# Juice_Rescue_v1_-_hw1_0_2.net
KiCad netlist of a schematic drawn in EAGLE
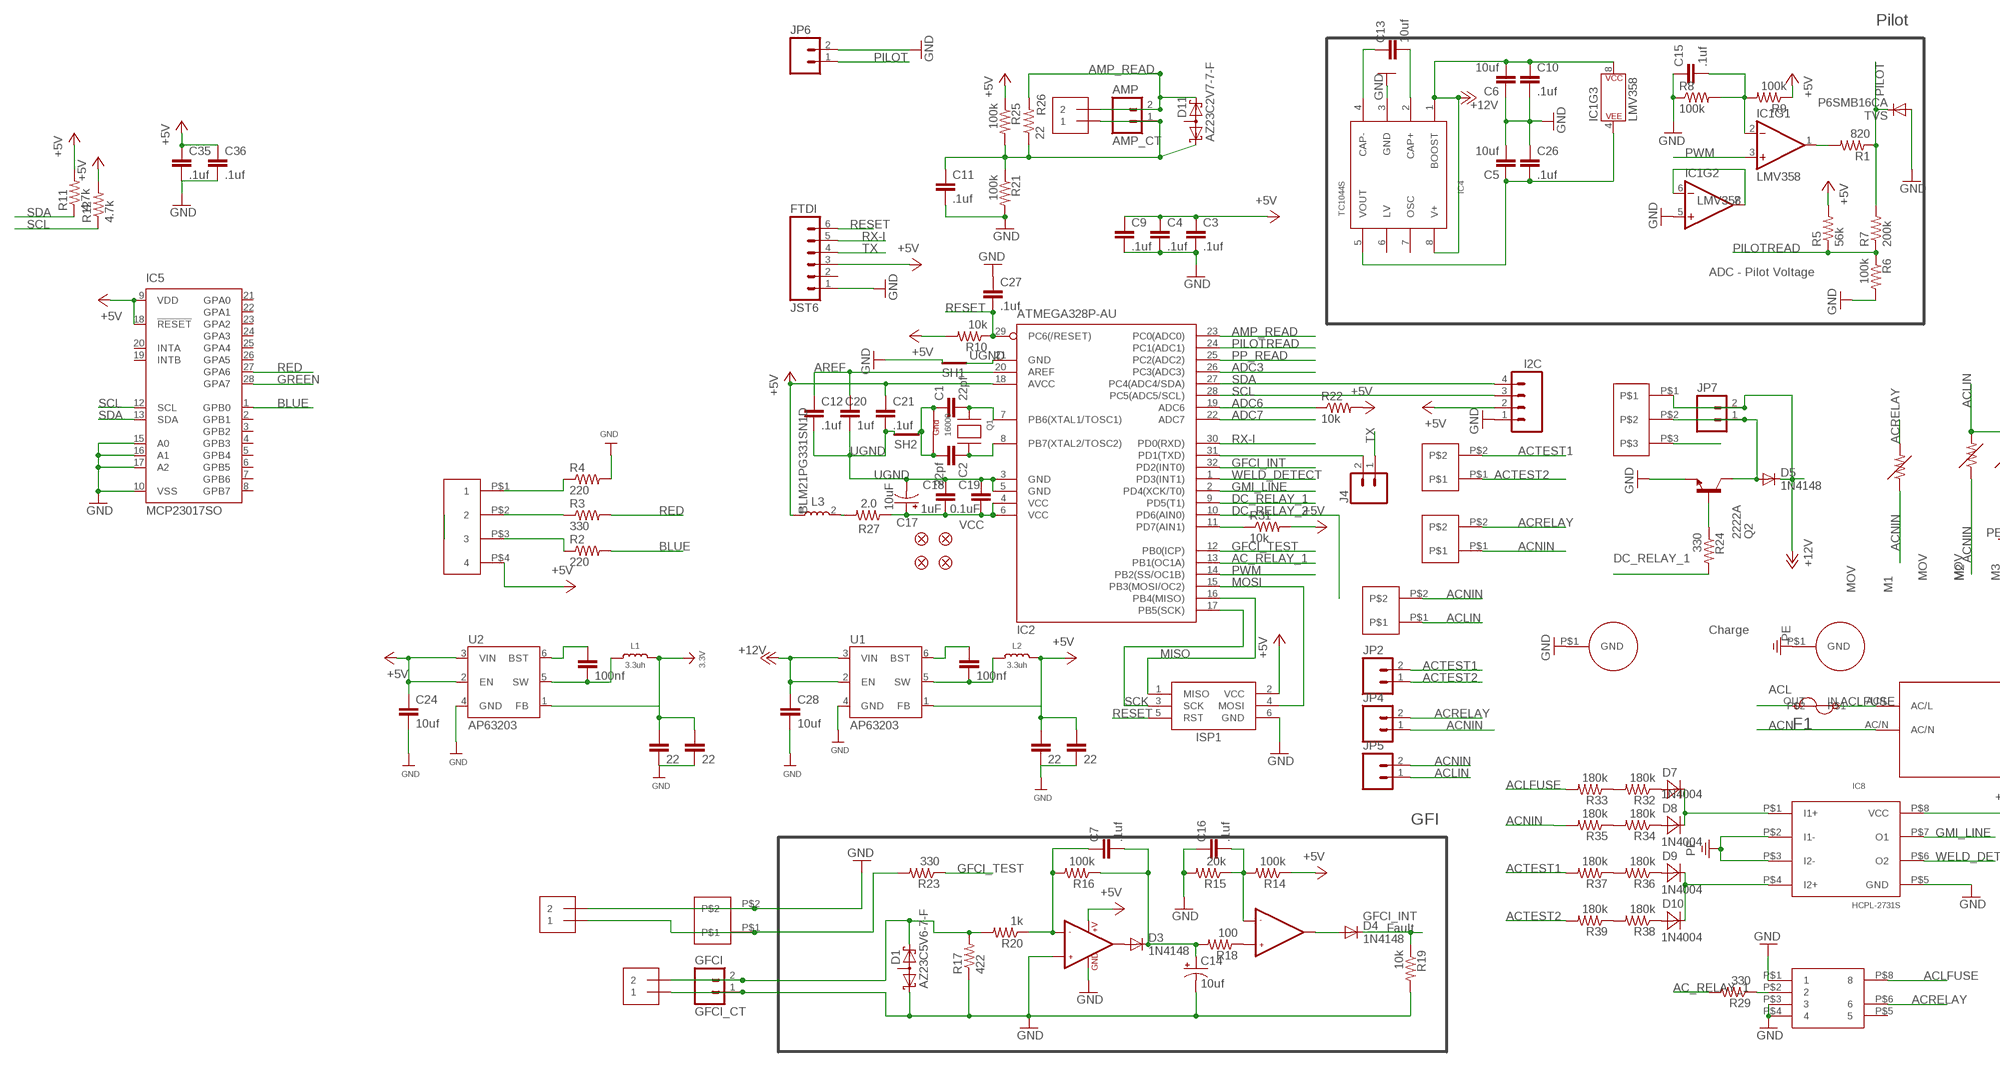
[diagram p0: schematic, sheet 1, part 1 of 2]
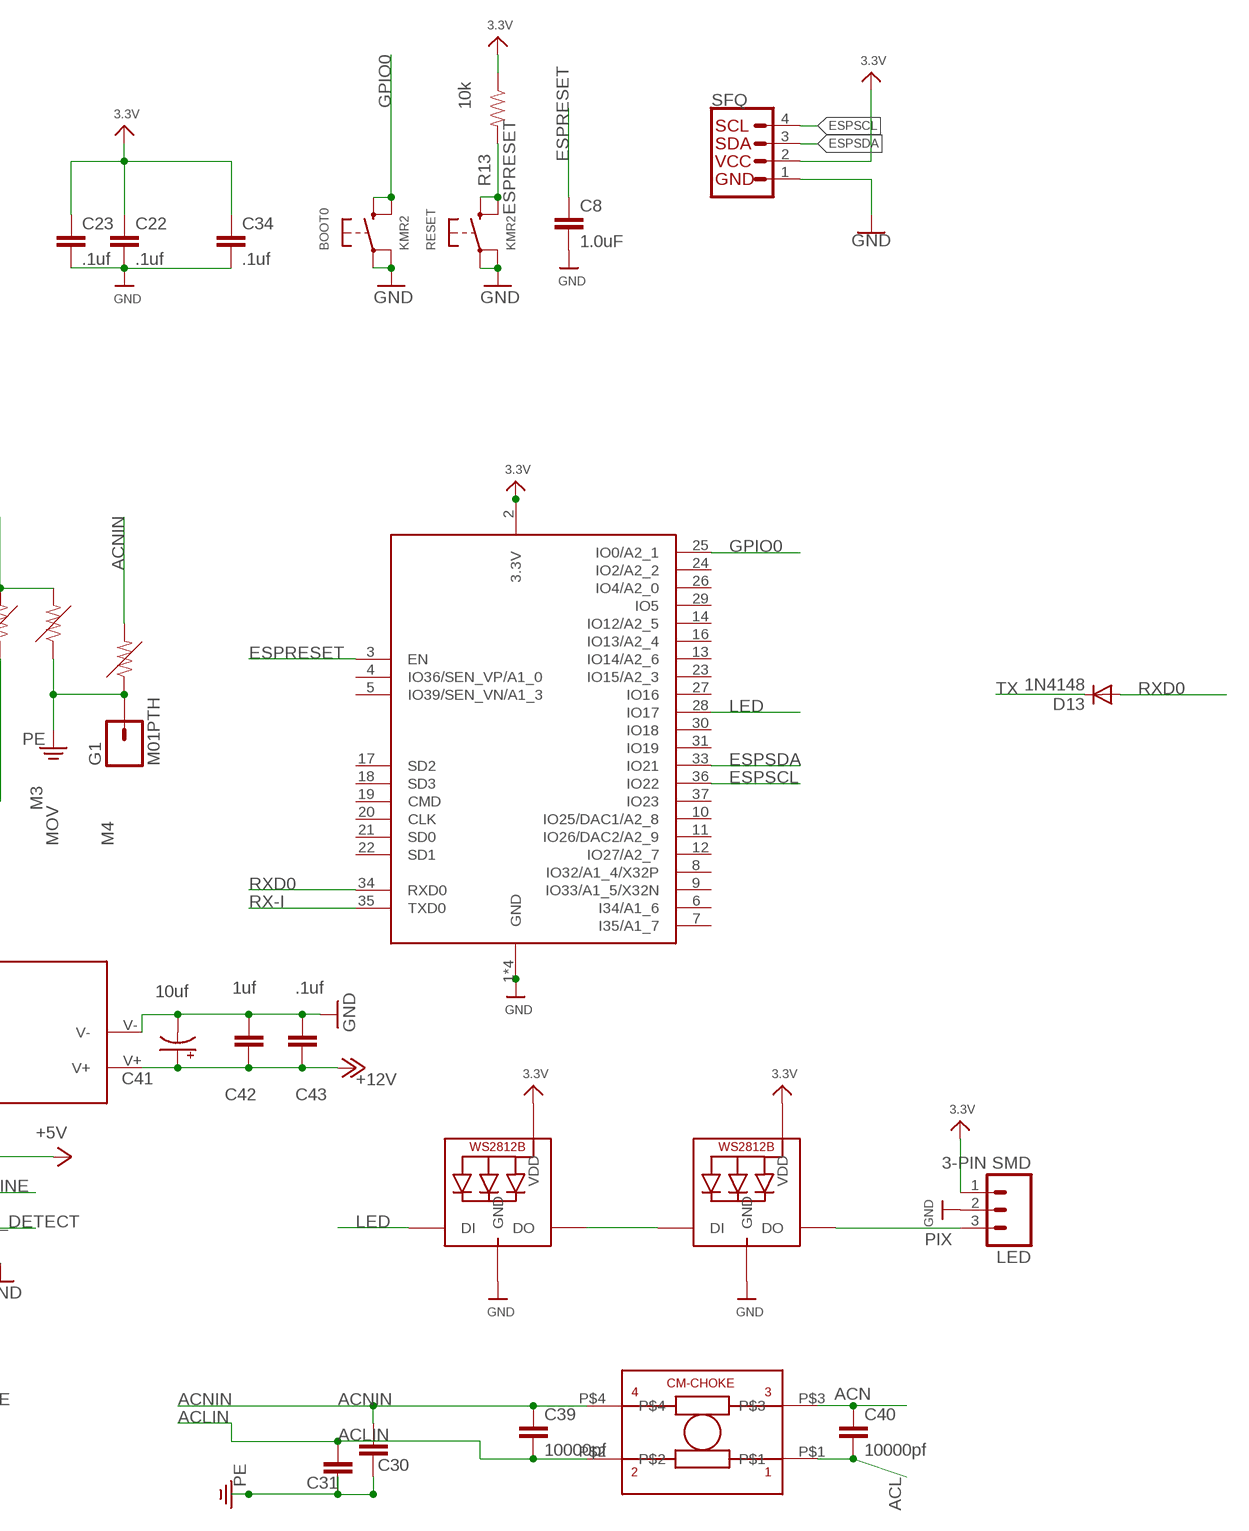
[diagram p1: schematic, sheet 1, part 2 of 2]

(export (version "E")
  (design (tool "Eeschema 10.0.6"))
  (components
    (comp (ref "AC")
      (value "AMPAC")
      (footprint "eagle-import:AMPAC")
      (libsource (lib "eagle-import") (part "AMPAC"))
    )
    (comp (ref "AC_RELAY")
      (value "AMPAC")
      (footprint "eagle-import:AMPAC")
      (libsource (lib "eagle-import") (part "AMPAC"))
    )
    (comp (ref "AC_TEST")
      (value "AMPAC")
      (footprint "eagle-import:AMPAC")
      (libsource (lib "eagle-import") (part "AMPAC"))
    )
    (comp (ref "AMP")
      (value "AMP_CT")
      (footprint "eagle-import:MOLEX_2")
      (libsource (lib "eagle-import") (part "MOLEX_2"))
    )
    (comp (ref "BOOT0")
      (value "KMR2")
      (footprint "eagle-import:BTN_KMR2_4.6X2.8")
      (libsource (lib "eagle-import") (part "SWITCH_TACT_SMT4.6X2.8"))
    )
    (comp (ref "C1")
      (value "22pf")
      (footprint "eagle-import:0805")
      (libsource (lib "eagle-import") (part "CAP0805"))
    )
    (comp (ref "C2")
      (value "22pf")
      (footprint "eagle-import:0805")
      (libsource (lib "eagle-import") (part "CAP0805"))
    )
    (comp (ref "C3")
      (value ".1uf")
      (footprint "eagle-import:0805")
      (libsource (lib "eagle-import") (part "CAP0805"))
    )
    (comp (ref "C4")
      (value ".1uf")
      (footprint "eagle-import:0805")
      (libsource (lib "eagle-import") (part "CAP0805"))
    )
    (comp (ref "C5")
      (value "10uf")
      (footprint "eagle-import:0805")
      (libsource (lib "eagle-import") (part "CAP0805"))
    )
    (comp (ref "C6")
      (value "10uf")
      (footprint "eagle-import:0805")
      (libsource (lib "eagle-import") (part "CAP0805"))
    )
    (comp (ref "C7")
      (value ".1uf")
      (footprint "eagle-import:0805")
      (libsource (lib "eagle-import") (part "CAP0805"))
    )
    (comp (ref "C8")
      (value "1.0uF")
      (footprint "eagle-import:0805")
      (libsource (lib "eagle-import") (part "1.0UF-0805-25V-(+80/-20%)"))
    )
    (comp (ref "C9")
      (value ".1uf")
      (footprint "eagle-import:0805")
      (libsource (lib "eagle-import") (part "CAP0805"))
    )
    (comp (ref "C10")
      (value ".1uf")
      (footprint "eagle-import:0805")
      (libsource (lib "eagle-import") (part "CAP0805"))
    )
    (comp (ref "C11")
      (value ".1uf")
      (footprint "eagle-import:0805")
      (libsource (lib "eagle-import") (part "CAP0805"))
    )
    (comp (ref "C12")
      (value ".1uf")
      (footprint "eagle-import:0805")
      (libsource (lib "eagle-import") (part "CAP0805"))
    )
    (comp (ref "C13")
      (value "10uf")
      (footprint "eagle-import:0805")
      (libsource (lib "eagle-import") (part "CAP0805"))
    )
    (comp (ref "C14")
      (value "10uf")
      (footprint "eagle-import:EIA3216")
      (libsource (lib "eagle-import") (part "CAP_POL1206"))
    )
    (comp (ref "C15")
      (value ".1uf")
      (footprint "eagle-import:0805")
      (libsource (lib "eagle-import") (part "CAP0805"))
    )
    (comp (ref "C16")
      (value ".1uf")
      (footprint "eagle-import:0805")
      (libsource (lib "eagle-import") (part "CAP0805"))
    )
    (comp (ref "C17")
      (value "10uF")
      (footprint "eagle-import:0603-POLAR")
      (libsource (lib "eagle-import") (part "10UF-POLAR-0603-6.3V-20%(TANT)"))
    )
    (comp (ref "C18")
      (value "1uF")
      (footprint "eagle-import:0805")
      (libsource (lib "eagle-import") (part "CAP0805"))
    )
    (comp (ref "C19")
      (value "0.1uF")
      (footprint "eagle-import:0805")
      (libsource (lib "eagle-import") (part "CAP0805"))
    )
    (comp (ref "C20")
      (value "1uf")
      (footprint "eagle-import:0805")
      (libsource (lib "eagle-import") (part "CAP0805"))
    )
    (comp (ref "C21")
      (value ".1uf")
      (footprint "eagle-import:0805")
      (libsource (lib "eagle-import") (part "CAP0805"))
    )
    (comp (ref "C22")
      (value ".1uf")
      (footprint "eagle-import:0805")
      (libsource (lib "eagle-import") (part "1.0UF-0805-25V-(+80/-20%)"))
    )
    (comp (ref "C23")
      (value ".1uf")
      (footprint "eagle-import:0805")
      (libsource (lib "eagle-import") (part "1.0UF-0805-25V-(+80/-20%)"))
    )
    (comp (ref "C24")
      (value "10uf")
      (footprint "eagle-import:0805")
      (libsource (lib "eagle-import") (part "1.0UF-0805-25V-(+80/-20%)"))
    )
    (comp (ref "C25")
      (value "22")
      (footprint "eagle-import:0805")
      (libsource (lib "eagle-import") (part "1.0UF-0805-25V-(+80/-20%)"))
    )
    (comp (ref "C26")
      (value ".1uf")
      (footprint "eagle-import:0805")
      (libsource (lib "eagle-import") (part "CAP0805"))
    )
    (comp (ref "C27")
      (value ".1uf")
      (footprint "eagle-import:0805")
      (libsource (lib "eagle-import") (part "CAP0805"))
    )
    (comp (ref "C28")
      (value "10uf")
      (footprint "eagle-import:0805")
      (libsource (lib "eagle-import") (part "1.0UF-0805-25V-(+80/-20%)"))
    )
    (comp (ref "C29")
      (value "22")
      (footprint "eagle-import:0805")
      (libsource (lib "eagle-import") (part "1.0UF-0805-25V-(+80/-20%)"))
    )
    (comp (ref "C30")
      (value "100nf")
      (footprint "eagle-import:0805")
      (libsource (lib "eagle-import") (part "1.0UF-0805-25V-(+80/-20%)"))
    )
    (comp (ref "C31")
      (value "22")
      (footprint "eagle-import:0805")
      (libsource (lib "eagle-import") (part "1.0UF-0805-25V-(+80/-20%)"))
    )
    (comp (ref "C32")
      (value "100nf")
      (footprint "eagle-import:0805")
      (libsource (lib "eagle-import") (part "1.0UF-0805-25V-(+80/-20%)"))
    )
    (comp (ref "C33")
      (value "22")
      (footprint "eagle-import:0805")
      (libsource (lib "eagle-import") (part "1.0UF-0805-25V-(+80/-20%)"))
    )
    (comp (ref "C34")
      (value ".1uf")
      (footprint "eagle-import:0805")
      (libsource (lib "eagle-import") (part "1.0UF-0805-25V-(+80/-20%)"))
    )
    (comp (ref "C35")
      (value ".1uf")
      (footprint "eagle-import:0805")
      (libsource (lib "eagle-import") (part "CAP0805"))
    )
    (comp (ref "C36")
      (value ".1uf")
      (footprint "eagle-import:0805")
      (libsource (lib "eagle-import") (part "CAP0805"))
    )
    (comp (ref "C37")
      (value "1000pf")
      (footprint "eagle-import:DK1E3EA")
      (libsource (lib "eagle-import") (part "DK1"))
    )
    (comp (ref "C38")
      (value "1000pf")
      (footprint "eagle-import:DK1E3EA")
      (libsource (lib "eagle-import") (part "DK1"))
    )
    (comp (ref "C39")
      (value "10000pf")
      (footprint "eagle-import:C7.5B4")
      (libsource (lib "eagle-import") (part "C7.5/4"))
    )
    (comp (ref "C40")
      (value "10000pf")
      (footprint "eagle-import:C7.5B4")
      (libsource (lib "eagle-import") (part "C7.5/4"))
    )
    (comp (ref "C41")
      (value "10uf")
      (footprint "eagle-import:EIA3216")
      (libsource (lib "eagle-import") (part "CAP_POL1206"))
    )
    (comp (ref "C42")
      (value "1uf")
      (footprint "eagle-import:0805")
      (libsource (lib "eagle-import") (part "CAP0805"))
    )
    (comp (ref "C43")
      (value ".1uf")
      (footprint "eagle-import:0805")
      (libsource (lib "eagle-import") (part "CAP0805"))
    )
    (comp (ref "D1")
      (value "AZ23C5V6-7-F")
      (footprint "eagle-import:SOT23")
      (libsource (lib "eagle-import") (part "BAS40-06"))
    )
    (comp (ref "D3")
      (value "1N4148")
      (footprint "eagle-import:SOD123")
      (libsource (lib "eagle-import") (part "DIODE-SOD123"))
    )
    (comp (ref "D4")
      (value "1N4148")
      (footprint "eagle-import:SOD123")
      (libsource (lib "eagle-import") (part "DIODE-SOD123"))
    )
    (comp (ref "D5")
      (value "1N4148")
      (footprint "eagle-import:SOD123")
      (libsource (lib "eagle-import") (part "DIODE-SOD123"))
    )
    (comp (ref "D7")
      (value "1N4004")
      (footprint "eagle-import:SMA")
      (libsource (lib "eagle-import") (part "MBRA340T3"))
    )
    (comp (ref "D8")
      (value "1N4004")
      (footprint "eagle-import:SMA")
      (libsource (lib "eagle-import") (part "MBRA340T3"))
    )
    (comp (ref "D9")
      (value "1N4004")
      (footprint "eagle-import:SMA")
      (libsource (lib "eagle-import") (part "MBRA340T3"))
    )
    (comp (ref "D10")
      (value "1N4004")
      (footprint "eagle-import:SMA")
      (libsource (lib "eagle-import") (part "MBRA340T3"))
    )
    (comp (ref "D11")
      (value "AZ23C2V7-7-F")
      (footprint "eagle-import:SOT23")
      (libsource (lib "eagle-import") (part "BAS40-06"))
    )
    (comp (ref "D13")
      (value "1N4148")
      (footprint "eagle-import:SOD123")
      (libsource (lib "eagle-import") (part "DIODE-SOD123"))
    )
    (comp (ref "F1")
      (value "BEL1.6AFUSE")
      (footprint "eagle-import:BELFUSE1A")
      (libsource (lib "eagle-import") (part "BEL1AFUSE"))
    )
    (comp (ref "FID1")
      (value "FIDUCIAL1X2.5")
      (footprint "eagle-import:FIDUCIAL-1X2.5")
      (libsource (lib "eagle-import") (part "FIDUCIAL1X2.5"))
    )
    (comp (ref "FID2")
      (value "FIDUCIAL1X2.5")
      (footprint "eagle-import:FIDUCIAL-1X2.5")
      (libsource (lib "eagle-import") (part "FIDUCIAL1X2.5"))
    )
    (comp (ref "FID3")
      (value "FIDUCIAL1X2.5")
      (footprint "eagle-import:FIDUCIAL-1X2.5")
      (libsource (lib "eagle-import") (part "FIDUCIAL1X2.5"))
    )
    (comp (ref "FID4")
      (value "FIDUCIAL1X2.5")
      (footprint "eagle-import:FIDUCIAL-1X2.5")
      (libsource (lib "eagle-import") (part "FIDUCIAL1X2.5"))
    )
    (comp (ref "FTDI")
      (value "JST6")
      (footprint "eagle-import:JST6")
      (libsource (lib "eagle-import") (part "JST6"))
    )
    (comp (ref "G1")
      (value "M01PTH")
      (footprint "eagle-import:1X01")
      (libsource (lib "eagle-import") (part "M01PTH"))
    )
    (comp (ref "GFCI")
      (value "GFCI_CT")
      (footprint "eagle-import:MOLEX_2")
      (libsource (lib "eagle-import") (part "MOLEX_2"))
    )
    (comp (ref "I2C")
      (value "M04JST-PTH-VERT")
      (footprint "eagle-import:JST-4-PTH-VERT")
      (libsource (lib "eagle-import") (part "M04JST-PTH-VERT"))
    )
    (comp (ref "IC1")
      (value "LMV358")
      (footprint "eagle-import:SO08")
      (libsource (lib "eagle-import") (part "LMV358SOIC"))
    )
    (comp (ref "IC2")
      (value "ATMEGA328P-AU")
      (footprint "eagle-import:TQFP32-08")
      (fields (field (name "MPN") "ATMEGA8-16AU"))
      (libsource (lib "eagle-import") (part "MEGA8-AI"))
    )
    (comp (ref "IC3")
      (value "LM358")
      (footprint "eagle-import:SO08")
      (libsource (lib "eagle-import") (part "LMV358"))
    )
    (comp (ref "IC4")
      (value "TC1044S")
      (footprint "eagle-import:SO-8")
      (libsource (lib "eagle-import") (part "TC1044S"))
    )
    (comp (ref "IC5")
      (value "MCP23017SO")
      (footprint "eagle-import:SO28W")
      (libsource (lib "eagle-import") (part "MCP23017SO"))
    )
    (comp (ref "IC7")
      (value "AQH2223")
      (footprint "eagle-import:SIL8")
      (libsource (lib "eagle-import") (part "AQH2223"))
    )
    (comp (ref "IC8")
      (value "HCPL-2731S")
      (footprint "eagle-import:SIL8-2")
      (libsource (lib "eagle-import") (part "HCPL-2731S"))
    )
    (comp (ref "ISP1")
      (value "ISP1")
      (footprint "eagle-import:AVRISP")
      (libsource (lib "eagle-import") (part "AVRISP-6"))
    )
    (comp (ref "J1")
      (value "1X2-3.5MM")
      (footprint "eagle-import:1X2-3.5MM")
      (libsource (lib "eagle-import") (part "1X2-3.5MM"))
    )
    (comp (ref "J2")
      (value "1X2-3.5MM")
      (footprint "eagle-import:1X2-3.5MM")
      (libsource (lib "eagle-import") (part "1X2-3.5MM"))
    )
    (comp (ref "J3")
      (value "1X2-3.5MM")
      (footprint "eagle-import:1X2-3.5MM")
      (libsource (lib "eagle-import") (part "1X2-3.5MM"))
    )
    (comp (ref "J4")
      (value "CONN_02")
      (footprint "eagle-import:1X02")
      (libsource (lib "eagle-import") (part "CONN_02"))
    )
    (comp (ref "JP2")
      (value "M025MM")
      (footprint "eagle-import:SCREWTERMINAL-5MM-2")
      (libsource (lib "eagle-import") (part "M025MM"))
    )
    (comp (ref "JP4")
      (value "M025MM")
      (footprint "eagle-import:SCREWTERMINAL-5MM-2")
      (libsource (lib "eagle-import") (part "M025MM"))
    )
    (comp (ref "JP5")
      (value "M025MM")
      (footprint "eagle-import:SCREWTERMINAL-5MM-2")
      (libsource (lib "eagle-import") (part "M025MM"))
    )
    (comp (ref "JP6")
      (value "M025MM")
      (footprint "eagle-import:SCREWTERMINAL-5MM-2")
      (libsource (lib "eagle-import") (part "M025MM"))
    )
    (comp (ref "JP7")
      (value "M025MM")
      (footprint "eagle-import:SCREWTERMINAL-5MM-2")
      (libsource (lib "eagle-import") (part "M025MM"))
    )
    (comp (ref "L1")
      (value "3.3uh")
      (footprint "eagle-import:MICROBUILDER_INDUCTOR_5X5MM_NR5040_NOTHERMALS")
      (libsource (lib "eagle-import") (part "MICROBUILDER_INDUCTORNR5040"))
    )
    (comp (ref "L2")
      (value "3.3uh")
      (footprint "eagle-import:MICROBUILDER_INDUCTOR_5X5MM_NR5040_NOTHERMALS")
      (libsource (lib "eagle-import") (part "MICROBUILDER_INDUCTORNR5040"))
    )
    (comp (ref "L3")
      (value "BLM21PG331SN1D")
      (footprint "eagle-import:INDC2012X87")
      (fields (field (name "MF") "Murata"))
      (libsource (lib "eagle-import") (part "BLM21PG331SN1D"))
    )
    (comp (ref "LED")
      (value "3-PIN SMD")
      (footprint "eagle-import:JST-3-SMD")
      (libsource (lib "eagle-import") (part "M03JST-SMD"))
    )
    (comp (ref "LED1")
      (value "WS2812B3535")
      (footprint "eagle-import:LED3535")
      (libsource (lib "eagle-import") (part "WS2812B3535"))
    )
    (comp (ref "LED2")
      (value "WS2812B3535")
      (footprint "eagle-import:LED3535")
      (libsource (lib "eagle-import") (part "WS2812B3535"))
    )
    (comp (ref "M1")
      (value "MOV")
      (footprint "eagle-import:MOV")
      (libsource (lib "eagle-import") (part "MOV"))
    )
    (comp (ref "M2")
      (value "MOV")
      (footprint "eagle-import:MOV")
      (libsource (lib "eagle-import") (part "MOV"))
    )
    (comp (ref "M3")
      (value "MOV")
      (footprint "eagle-import:MOV")
      (libsource (lib "eagle-import") (part "MOV"))
    )
    (comp (ref "M4")
      (value "MOV")
      (footprint "eagle-import:MOV")
      (libsource (lib "eagle-import") (part "MOV"))
    )
    (comp (ref "PILOT")
      (value "AMP3POS")
      (footprint "eagle-import:AMP3POS")
      (libsource (lib "eagle-import") (part "AMP3POS"))
    )
    (comp (ref "PS1")
      (value "IRM-10-5")
      (footprint "eagle-import:IRM-10-5")
      (libsource (lib "eagle-import") (part "IRM-10-5"))
    )
    (comp (ref "Q1")
      (value "16000")
      (footprint "eagle-import:NX3225")
      (libsource (lib "eagle-import") (part "XTAL-4-3225"))
    )
    (comp (ref "Q2")
      (value "2222A")
      (footprint "eagle-import:SOT23")
      (libsource (lib "eagle-import") (part "BCX70SMD"))
    )
    (comp (ref "R1")
      (value "820")
      (footprint "eagle-import:0805")
      (libsource (lib "eagle-import") (part "RESISTOR0805-RES"))
    )
    (comp (ref "R2")
      (value "220")
      (footprint "eagle-import:0805")
      (libsource (lib "eagle-import") (part "RESISTOR0805-RES"))
    )
    (comp (ref "R3")
      (value "330")
      (footprint "eagle-import:0805")
      (libsource (lib "eagle-import") (part "RESISTOR0805-RES"))
    )
    (comp (ref "R4")
      (value "220")
      (footprint "eagle-import:0805")
      (libsource (lib "eagle-import") (part "RESISTOR0805-RES"))
    )
    (comp (ref "R5")
      (value "56k")
      (footprint "eagle-import:0805")
      (libsource (lib "eagle-import") (part "RESISTOR0805-RES"))
    )
    (comp (ref "R6")
      (value "100k")
      (footprint "eagle-import:0805")
      (libsource (lib "eagle-import") (part "RESISTOR0805-RES"))
    )
    (comp (ref "R7")
      (value "200k")
      (footprint "eagle-import:0805")
      (libsource (lib "eagle-import") (part "RESISTOR0805-RES"))
    )
    (comp (ref "R8")
      (value "100k")
      (footprint "eagle-import:0805")
      (libsource (lib "eagle-import") (part "RESISTOR0805-RES"))
    )
    (comp (ref "R9")
      (value "100k")
      (footprint "eagle-import:0805")
      (libsource (lib "eagle-import") (part "RESISTOR0805-RES"))
    )
    (comp (ref "R10")
      (value "10k")
      (footprint "eagle-import:0805")
      (libsource (lib "eagle-import") (part "RESISTOR0805-RES"))
    )
    (comp (ref "R11")
      (value "4.7k")
      (footprint "eagle-import:0805")
      (libsource (lib "eagle-import") (part "RESISTOR0805-RES"))
    )
    (comp (ref "R12")
      (value "4.7k")
      (footprint "eagle-import:0805")
      (libsource (lib "eagle-import") (part "RESISTOR0805-RES"))
    )
    (comp (ref "R13")
      (value "10k")
      (footprint "eagle-import:0805")
      (libsource (lib "eagle-import") (part "RESISTOR0805"))
    )
    (comp (ref "R14")
      (value "100k")
      (footprint "eagle-import:0805")
      (libsource (lib "eagle-import") (part "RESISTOR0805-RES"))
    )
    (comp (ref "R15")
      (value "20k")
      (footprint "eagle-import:0805")
      (libsource (lib "eagle-import") (part "RESISTOR0805-RES"))
    )
    (comp (ref "R16")
      (value "100k")
      (footprint "eagle-import:0805")
      (libsource (lib "eagle-import") (part "RESISTOR0805-RES"))
    )
    (comp (ref "R17")
      (value "422")
      (footprint "eagle-import:0805")
      (libsource (lib "eagle-import") (part "RESISTOR0805-RES"))
    )
    (comp (ref "R18")
      (value "100")
      (footprint "eagle-import:0805")
      (libsource (lib "eagle-import") (part "RESISTOR0805-RES"))
    )
    (comp (ref "R19")
      (value "10k")
      (footprint "eagle-import:0805")
      (libsource (lib "eagle-import") (part "RESISTOR0805-RES"))
    )
    (comp (ref "R20")
      (value "1k")
      (footprint "eagle-import:0805")
      (libsource (lib "eagle-import") (part "RESISTOR0805-RES"))
    )
    (comp (ref "R21")
      (value "100k")
      (footprint "eagle-import:0805")
      (libsource (lib "eagle-import") (part "RESISTOR0805-RES"))
    )
    (comp (ref "R22")
      (value "10k")
      (footprint "eagle-import:0805")
      (libsource (lib "eagle-import") (part "RESISTOR0805-RES"))
    )
    (comp (ref "R23")
      (value "330")
      (footprint "eagle-import:0805")
      (libsource (lib "eagle-import") (part "RESISTOR0805-RES"))
    )
    (comp (ref "R24")
      (value "330")
      (footprint "eagle-import:0805")
      (libsource (lib "eagle-import") (part "RESISTOR0805-RES"))
    )
    (comp (ref "R25")
      (value "100k")
      (footprint "eagle-import:0805")
      (libsource (lib "eagle-import") (part "RESISTOR0805-RES"))
    )
    (comp (ref "R26")
      (value "22")
      (footprint "eagle-import:R1206")
      (libsource (lib "eagle-import") (part "R-US_R1206"))
    )
    (comp (ref "R27")
      (value "2.0")
      (footprint "eagle-import:0805")
      (libsource (lib "eagle-import") (part "RESISTOR0805-RES"))
    )
    (comp (ref "R29")
      (value "330")
      (footprint "eagle-import:0805")
      (libsource (lib "eagle-import") (part "RESISTOR0805-RES"))
    )
    (comp (ref "R31")
      (value "10k")
      (footprint "eagle-import:0805")
      (libsource (lib "eagle-import") (part "RESISTOR0805-RES"))
    )
    (comp (ref "R32")
      (value "180k")
      (footprint "eagle-import:1210")
      (libsource (lib "eagle-import") (part "0.1OHM-1/2W-1%(1210)"))
    )
    (comp (ref "R33")
      (value "180k")
      (footprint "eagle-import:1210")
      (libsource (lib "eagle-import") (part "0.1OHM-1/2W-1%(1210)"))
    )
    (comp (ref "R34")
      (value "180k")
      (footprint "eagle-import:1210")
      (libsource (lib "eagle-import") (part "0.1OHM-1/2W-1%(1210)"))
    )
    (comp (ref "R35")
      (value "180k")
      (footprint "eagle-import:1210")
      (libsource (lib "eagle-import") (part "0.1OHM-1/2W-1%(1210)"))
    )
    (comp (ref "R36")
      (value "180k")
      (footprint "eagle-import:1210")
      (libsource (lib "eagle-import") (part "0.1OHM-1/2W-1%(1210)"))
    )
    (comp (ref "R37")
      (value "180k")
      (footprint "eagle-import:1210")
      (libsource (lib "eagle-import") (part "0.1OHM-1/2W-1%(1210)"))
    )
    (comp (ref "R38")
      (value "180k")
      (footprint "eagle-import:1210")
      (libsource (lib "eagle-import") (part "0.1OHM-1/2W-1%(1210)"))
    )
    (comp (ref "R39")
      (value "180k")
      (footprint "eagle-import:1210")
      (libsource (lib "eagle-import") (part "0.1OHM-1/2W-1%(1210)"))
    )
    (comp (ref "RESET")
      (value "KMR2")
      (footprint "eagle-import:BTN_KMR2_4.6X2.8")
      (libsource (lib "eagle-import") (part "SWITCH_TACT_SMT4.6X2.8"))
    )
    (comp (ref "RF1")
      (value "RN214-0.3-02-47M")
      (footprint "eagle-import:RN214-0.3-02-47M")
      (libsource (lib "eagle-import") (part "RN214-0.3-02-47M"))
    )
    (comp (ref "RGB_LED")
      (value "4X1MMRIBBON")
      (footprint "eagle-import:4X1MMRIBBON")
      (libsource (lib "eagle-import") (part "4X1MMRIBBON"))
    )
    (comp (ref "SFQ")
      (value "QWIIC_CONNECTORJS-1MM")
      (footprint "eagle-import:JST04_1MM_RA")
      (libsource (lib "eagle-import") (part "QWIIC_CONNECTORJS-1MM"))
    )
    (comp (ref "SH1")
      (value "SHORT-HT5")
      (footprint "eagle-import:SHORT_TOP-50")
      (libsource (lib "eagle-import") (part "SHORT-HT5"))
    )
    (comp (ref "SH2")
      (value "SHORT-HT5")
      (footprint "eagle-import:SHORT_TOP-50")
      (libsource (lib "eagle-import") (part "SHORT-HT5"))
    )
    (comp (ref "TEST_COIL")
      (value "AMPAC")
      (footprint "eagle-import:AMPAC")
      (libsource (lib "eagle-import") (part "AMPAC"))
    )
    (comp (ref "TVS")
      (value "P6SMB16CA")
      (footprint "eagle-import:SMB")
      (libsource (lib "eagle-import") (part "DIODE-SMB"))
    )
    (comp (ref "U$3")
      (value "HOLE")
      (footprint "eagle-import:HOLE")
      (libsource (lib "eagle-import") (part "HOLE"))
    )
    (comp (ref "U$9")
      (value "HOLE")
      (footprint "eagle-import:HOLE")
      (libsource (lib "eagle-import") (part "HOLE"))
    )
    (comp (ref "U1")
      (value "AP63203")
      (footprint "eagle-import:SOT23-6")
      (libsource (lib "eagle-import") (part "AP63203"))
    )
    (comp (ref "U2")
      (value "AP63203")
      (footprint "eagle-import:SOT23-6")
      (libsource (lib "eagle-import") (part "AP63203"))
    )
    (comp (ref "X2")
      (value "ESP32-WROOM-32")
      (footprint "eagle-import:WROOM32_SKINNY")
      (libsource (lib "eagle-import") (part "ESP32_WROOM32_SKINNY"))
    )
  )
  (nets
    (net (code "1") (name "+5V") (class "Default")
      (node (ref "C21") (pin "1") (pinfunction "1_1") (pintype "passive"))
      (node (ref "C24") (pin "1") (pinfunction "1_1") (pintype "passive"))
      (node (ref "C29") (pin "1") (pinfunction "1_1") (pintype "passive"))
      (node (ref "C3") (pin "1") (pinfunction "1_1") (pintype "passive"))
      (node (ref "C33") (pin "1") (pinfunction "1_1") (pintype "passive"))
      (node (ref "C35") (pin "1") (pinfunction "1_1") (pintype "passive"))
      (node (ref "C36") (pin "1") (pinfunction "1_1") (pintype "passive"))
      (node (ref "C4") (pin "1") (pinfunction "1_1") (pintype "passive"))
      (node (ref "C9") (pin "1") (pinfunction "1_1") (pintype "passive"))
      (node (ref "FTDI") (pin "3") (pinfunction "3_3") (pintype "passive"))
      (node (ref "I2C") (pin "2") (pinfunction "2_2") (pintype "passive"))
      (node (ref "IC2") (pin "18") (pinfunction "AVCC_18") (pintype "power_in"))
      (node (ref "IC3") (pin "8") (pinfunction "+V_8") (pintype "power_in"))
      (node (ref "IC5") (pin "18") (pinfunction "~{RESET}_18") (pintype "input"))
      (node (ref "IC5") (pin "9") (pinfunction "VDD_9") (pintype "power_in"))
      (node (ref "IC8") (pin "P$8") (pinfunction "VCC_P$8") (pintype "bidirectional"))
      (node (ref "ISP1") (pin "2") (pinfunction "VCC_2") (pintype "power_in"))
      (node (ref "L2") (pin "P$2") (pinfunction "2_P$2") (pintype "passive"))
      (node (ref "L3") (pin "1") (pinfunction "1_1") (pintype "passive"))
      (node (ref "R10") (pin "2") (pinfunction "2_2") (pintype "passive"))
      (node (ref "R11") (pin "2") (pinfunction "2_2") (pintype "passive"))
      (node (ref "R12") (pin "2") (pinfunction "2_2") (pintype "passive"))
      (node (ref "R14") (pin "1") (pinfunction "1_1") (pintype "passive"))
      (node (ref "R22") (pin "2") (pinfunction "2_2") (pintype "passive"))
      (node (ref "R25") (pin "1") (pinfunction "1_1") (pintype "passive"))
      (node (ref "R31") (pin "2") (pinfunction "2_2") (pintype "passive"))
      (node (ref "R5") (pin "2") (pinfunction "2_2") (pintype "passive"))
      (node (ref "R9") (pin "1") (pinfunction "1_1") (pintype "passive"))
      (node (ref "RGB_LED") (pin "P$4") (pinfunction "4_P$4") (pintype "bidirectional"))
      (node (ref "U1") (pin "1") (pinfunction "FB_1") (pintype "bidirectional"))
      (node (ref "U2") (pin "2") (pinfunction "EN_2") (pintype "bidirectional"))
      (node (ref "U2") (pin "3") (pinfunction "VIN_3") (pintype "bidirectional"))
    )
    (net (code "2") (name "+12V") (class "Default")
      (node (ref "C10") (pin "1") (pinfunction "1_1") (pintype "passive"))
      (node (ref "C28") (pin "1") (pinfunction "1_1") (pintype "passive"))
      (node (ref "C41") (pin "A") (pinfunction "+_A") (pintype "passive"))
      (node (ref "C42") (pin "1") (pinfunction "1_1") (pintype "passive"))
      (node (ref "C43") (pin "2") (pinfunction "2_2") (pintype "passive"))
      (node (ref "C6") (pin "2") (pinfunction "2_2") (pintype "passive"))
      (node (ref "D5") (pin "C") (pinfunction "C_C") (pintype "passive"))
      (node (ref "IC1") (pin "8") (pinfunction "P$V+_8") (pintype "bidirectional"))
      (node (ref "IC4") (pin "1") (pinfunction "BOOST_1") (pintype "bidirectional"))
      (node (ref "IC4") (pin "8") (pinfunction "V+_8") (pintype "bidirectional"))
      (node (ref "JP7") (pin "2") (pinfunction "2_2") (pintype "passive"))
      (node (ref "PILOT") (pin "P$1") (pinfunction "P$1_P$1") (pintype "bidirectional"))
      (node (ref "PS1") (pin "V+") (pinfunction "V+_V+") (pintype "bidirectional"))
      (node (ref "U1") (pin "2") (pinfunction "EN_2") (pintype "bidirectional"))
      (node (ref "U1") (pin "3") (pinfunction "VIN_3") (pintype "bidirectional"))
    )
    (net (code "3") (name "/ACL") (class "Default")
      (node (ref "C40") (pin "2") (pinfunction "2_2") (pintype "passive"))
      (node (ref "F1") (pin "OUT") (pinfunction "P$1_OUT") (pintype "bidirectional"))
      (node (ref "RF1") (pin "P$1") (pinfunction "P$1_P$1") (pintype "bidirectional"))
    )
    (net (code "4") (name "/ACLFUSE") (class "Default")
      (node (ref "F1") (pin "IN") (pinfunction "P$2_IN") (pintype "bidirectional"))
      (node (ref "IC7") (pin "P$8") (pinfunction "8_P$8") (pintype "bidirectional"))
      (node (ref "PS1") (pin "AC/L") (pinfunction "AC/L_AC/L") (pintype "bidirectional"))
      (node (ref "R33") (pin "2") (pinfunction "2_2") (pintype "passive"))
    )
    (net (code "5") (name "/ACLIN") (class "Default")
      (node (ref "AC") (pin "P$1") (pinfunction "P$1_P$1") (pintype "bidirectional"))
      (node (ref "C38") (pin "P$2") (pinfunction "2_P$2") (pintype "passive"))
      (node (ref "C39") (pin "2") (pinfunction "2_2") (pintype "passive"))
      (node (ref "JP5") (pin "1") (pinfunction "1_1") (pintype "passive"))
      (node (ref "M2") (pin "P$2") (pinfunction "2_P$2") (pintype "passive"))
      (node (ref "M3") (pin "P$2") (pinfunction "2_P$2") (pintype "passive"))
      (node (ref "RF1") (pin "P$2") (pinfunction "P$2_P$2") (pintype "bidirectional"))
    )
    (net (code "6") (name "/ACN") (class "Default")
      (node (ref "C40") (pin "1") (pinfunction "1_1") (pintype "passive"))
      (node (ref "PS1") (pin "AC/N") (pinfunction "AC/N_AC/N") (pintype "bidirectional"))
      (node (ref "RF1") (pin "P$3") (pinfunction "P$3_P$3") (pintype "bidirectional"))
    )
    (net (code "7") (name "/ACNIN") (class "Default")
      (node (ref "AC") (pin "P$2") (pinfunction "P$2_P$2") (pintype "bidirectional"))
      (node (ref "AC_RELAY") (pin "P$1") (pinfunction "P$1_P$1") (pintype "bidirectional"))
      (node (ref "C37") (pin "P$2") (pinfunction "2_P$2") (pintype "passive"))
      (node (ref "C39") (pin "1") (pinfunction "1_1") (pintype "passive"))
      (node (ref "JP4") (pin "1") (pinfunction "1_1") (pintype "passive"))
      (node (ref "JP5") (pin "2") (pinfunction "2_2") (pintype "passive"))
      (node (ref "M1") (pin "P$1") (pinfunction "1_P$1") (pintype "passive"))
      (node (ref "M2") (pin "P$1") (pinfunction "1_P$1") (pintype "passive"))
      (node (ref "M4") (pin "P$2") (pinfunction "2_P$2") (pintype "passive"))
      (node (ref "R35") (pin "2") (pinfunction "2_2") (pintype "passive"))
      (node (ref "RF1") (pin "P$4") (pinfunction "P$4_P$4") (pintype "bidirectional"))
    )
    (net (code "8") (name "/ACRELAY") (class "Default")
      (node (ref "AC_RELAY") (pin "P$2") (pinfunction "P$2_P$2") (pintype "bidirectional"))
      (node (ref "IC7") (pin "P$6") (pinfunction "6_P$6") (pintype "bidirectional"))
      (node (ref "JP4") (pin "2") (pinfunction "2_2") (pintype "passive"))
      (node (ref "M1") (pin "P$2") (pinfunction "2_P$2") (pintype "passive"))
    )
    (net (code "9") (name "/ACTEST1") (class "Default")
      (node (ref "AC_TEST") (pin "P$2") (pinfunction "P$2_P$2") (pintype "bidirectional"))
      (node (ref "JP2") (pin "2") (pinfunction "2_2") (pintype "passive"))
      (node (ref "R37") (pin "2") (pinfunction "2_2") (pintype "passive"))
    )
    (net (code "10") (name "/ACTEST2") (class "Default")
      (node (ref "AC_TEST") (pin "P$1") (pinfunction "P$1_P$1") (pintype "bidirectional"))
      (node (ref "JP2") (pin "1") (pinfunction "1_1") (pintype "passive"))
      (node (ref "R39") (pin "2") (pinfunction "2_2") (pintype "passive"))
    )
    (net (code "11") (name "/AC_RELAY_1") (class "Default")
      (node (ref "IC2") (pin "13") (pinfunction "PB1(OC1A)_13") (pintype "bidirectional"))
      (node (ref "R29") (pin "2") (pinfunction "2_2") (pintype "passive"))
    )
    (net (code "12") (name "/ADC3") (class "Default")
      (node (ref "IC2") (pin "26") (pinfunction "PC3(ADC3)_26") (pintype "bidirectional"))
    )
    (net (code "13") (name "/ADC6") (class "Default")
      (node (ref "IC2") (pin "19") (pinfunction "ADC6_19") (pintype "bidirectional"))
      (node (ref "R22") (pin "1") (pinfunction "1_1") (pintype "passive"))
    )
    (net (code "14") (name "/ADC7") (class "Default")
      (node (ref "IC2") (pin "22") (pinfunction "ADC7_22") (pintype "bidirectional"))
    )
    (net (code "15") (name "/AMP_READ") (class "Default")
      (node (ref "AMP") (pin "2") (pinfunction "2_2") (pintype "passive"))
      (node (ref "D11") (pin "2") (pinfunction "K2_2") (pintype "passive"))
      (node (ref "IC2") (pin "23") (pinfunction "PC0(ADC0)_23") (pintype "bidirectional"))
      (node (ref "J3") (pin "2") (pinfunction "2_2") (pintype "passive"))
      (node (ref "R26") (pin "2") (pinfunction "2_2") (pintype "passive"))
    )
    (net (code "16") (name "/AREF") (class "Default")
      (node (ref "C12") (pin "1") (pinfunction "1_1") (pintype "passive"))
      (node (ref "C20") (pin "1") (pinfunction "1_1") (pintype "passive"))
      (node (ref "IC2") (pin "20") (pinfunction "AREF_20") (pintype "passive"))
    )
    (net (code "17") (name "/BLUE") (class "Default")
      (node (ref "IC5") (pin "1") (pinfunction "GPB0_1") (pintype "bidirectional"))
      (node (ref "R2") (pin "2") (pinfunction "2_2") (pintype "passive"))
    )
    (net (code "18") (name "/DC_RELAY_1") (class "Default")
      (node (ref "IC2") (pin "9") (pinfunction "PD5(T1)_9") (pintype "bidirectional"))
      (node (ref "R24") (pin "2") (pinfunction "2_2") (pintype "passive"))
    )
    (net (code "19") (name "/DC_RELAY_2") (class "Default")
      (node (ref "IC2") (pin "10") (pinfunction "PD6(AIN0)_10") (pintype "bidirectional"))
    )
    (net (code "20") (name "/ESPRESET") (class "Default")
      (node (ref "C8") (pin "1") (pinfunction "1_1") (pintype "passive"))
      (node (ref "R13") (pin "2") (pinfunction "2_2") (pintype "passive"))
      (node (ref "RESET") (pin "B") (pinfunction "S_B") (pintype "passive"))
      (node (ref "RESET") (pin "B'") (pinfunction "S1_B'") (pintype "passive"))
      (node (ref "X2") (pin "3") (pinfunction "EN_3") (pintype "input"))
    )
    (net (code "21") (name "/GFCI_INT") (class "Default")
      (node (ref "D4") (pin "C") (pinfunction "C_C") (pintype "passive"))
      (node (ref "IC2") (pin "32") (pinfunction "PD2(INT0)_32") (pintype "bidirectional"))
      (node (ref "R19") (pin "1") (pinfunction "1_1") (pintype "passive"))
    )
    (net (code "22") (name "/GFCI_TEST") (class "Default")
      (node (ref "IC2") (pin "12") (pinfunction "PB0(ICP)_12") (pintype "bidirectional"))
      (node (ref "R23") (pin "1") (pinfunction "1_1") (pintype "passive"))
    )
    (net (code "23") (name "/GMI_LINE") (class "Default")
      (node (ref "IC2") (pin "2") (pinfunction "PD4(XCK/T0)_2") (pintype "bidirectional"))
      (node (ref "IC8") (pin "P$7") (pinfunction "O1_P$7") (pintype "bidirectional"))
    )
    (net (code "24") (name "/GPIO0") (class "Default")
      (node (ref "BOOT0") (pin "B") (pinfunction "S_B") (pintype "passive"))
      (node (ref "BOOT0") (pin "B'") (pinfunction "S1_B'") (pintype "passive"))
      (node (ref "X2") (pin "25") (pinfunction "IO0/A2_1_25") (pintype "bidirectional"))
    )
    (net (code "25") (name "/GREEN") (class "Default")
      (node (ref "IC5") (pin "28") (pinfunction "GPA7_28") (pintype "bidirectional"))
    )
    (net (code "26") (name "/LED") (class "Default")
      (node (ref "LED1") (pin "1") (pinfunction "DI_1") (pintype "input"))
      (node (ref "X2") (pin "28") (pinfunction "IO17_28") (pintype "bidirectional"))
    )
    (net (code "27") (name "/MISO") (class "Default")
      (node (ref "IC2") (pin "16") (pinfunction "PB4(MISO)_16") (pintype "bidirectional"))
      (node (ref "ISP1") (pin "1") (pinfunction "MISO_1") (pintype "input"))
    )
    (net (code "28") (name "/MOSI") (class "Default")
      (node (ref "IC2") (pin "15") (pinfunction "PB3(MOSI/OC2)_15") (pintype "bidirectional"))
      (node (ref "ISP1") (pin "4") (pinfunction "MOSI_4") (pintype "output"))
    )
    (net (code "29") (name "/PILOT") (class "Default")
      (node (ref "JP6") (pin "1") (pinfunction "1_1") (pintype "passive"))
      (node (ref "PILOT") (pin "P$3") (pinfunction "P$3_P$3") (pintype "bidirectional"))
      (node (ref "R1") (pin "1") (pinfunction "1_1") (pintype "passive"))
      (node (ref "R7") (pin "2") (pinfunction "2_2") (pintype "passive"))
      (node (ref "TVS") (pin "C") (pinfunction "C_C") (pintype "passive"))
    )
    (net (code "30") (name "/PILOTREAD") (class "Default")
      (node (ref "IC2") (pin "24") (pinfunction "PC1(ADC1)_24") (pintype "bidirectional"))
      (node (ref "R5") (pin "1") (pinfunction "1_1") (pintype "passive"))
      (node (ref "R6") (pin "1") (pinfunction "1_1") (pintype "passive"))
      (node (ref "R7") (pin "1") (pinfunction "1_1") (pintype "passive"))
    )
    (net (code "31") (name "/PIX") (class "Default")
      (node (ref "LED") (pin "3") (pinfunction "3_3") (pintype "passive"))
      (node (ref "LED2") (pin "3") (pinfunction "DO_3") (pintype "output"))
    )
    (net (code "32") (name "/PP_READ") (class "Default")
      (node (ref "IC2") (pin "25") (pinfunction "PC2(ADC2)_25") (pintype "bidirectional"))
    )
    (net (code "33") (name "/PWM") (class "Default")
      (node (ref "IC1") (pin "3") (pinfunction "+IN_3") (pintype "input"))
      (node (ref "IC2") (pin "14") (pinfunction "PB2(SS/OC1B)_14") (pintype "bidirectional"))
    )
    (net (code "34") (name "/RED") (class "Default")
      (node (ref "IC5") (pin "27") (pinfunction "GPA6_27") (pintype "bidirectional"))
      (node (ref "R3") (pin "2") (pinfunction "2_2") (pintype "passive"))
    )
    (net (code "35") (name "/RESET") (class "Default")
      (node (ref "C27") (pin "2") (pinfunction "2_2") (pintype "passive"))
      (node (ref "FTDI") (pin "6") (pinfunction "6_6") (pintype "passive"))
      (node (ref "IC2") (pin "29") (pinfunction "PC6(/RESET)_29") (pintype "bidirectional"))
      (node (ref "ISP1") (pin "5") (pinfunction "RST_5") (pintype "output"))
      (node (ref "R10") (pin "1") (pinfunction "1_1") (pintype "passive"))
    )
    (net (code "36") (name "/RX-I") (class "Default")
      (node (ref "FTDI") (pin "5") (pinfunction "5_5") (pintype "passive"))
      (node (ref "IC2") (pin "30") (pinfunction "PD0(RXD)_30") (pintype "bidirectional"))
      (node (ref "X2") (pin "35") (pinfunction "TXD0_35") (pintype "output"))
    )
    (net (code "37") (name "/RXD0") (class "Default")
      (node (ref "D13") (pin "A") (pinfunction "A_A") (pintype "passive"))
      (node (ref "X2") (pin "34") (pinfunction "RXD0_34") (pintype "input"))
    )
    (net (code "38") (name "/SCK") (class "Default")
      (node (ref "IC2") (pin "17") (pinfunction "PB5(SCK)_17") (pintype "bidirectional"))
      (node (ref "ISP1") (pin "3") (pinfunction "SCK_3") (pintype "output"))
    )
    (net (code "39") (name "/SCL") (class "Default")
      (node (ref "I2C") (pin "3") (pinfunction "3_3") (pintype "passive"))
      (node (ref "IC2") (pin "28") (pinfunction "PC5(ADC5/SCL)_28") (pintype "bidirectional"))
      (node (ref "IC5") (pin "12") (pinfunction "SCL_12") (pintype "input"))
      (node (ref "R12") (pin "1") (pinfunction "1_1") (pintype "passive"))
    )
    (net (code "40") (name "/SDA") (class "Default")
      (node (ref "I2C") (pin "4") (pinfunction "4_4") (pintype "passive"))
      (node (ref "IC2") (pin "27") (pinfunction "PC4(ADC4/SDA)_27") (pintype "bidirectional"))
      (node (ref "IC5") (pin "13") (pinfunction "SDA_13") (pintype "bidirectional"))
      (node (ref "R11") (pin "1") (pinfunction "1_1") (pintype "passive"))
    )
    (net (code "41") (name "/TX") (class "Default")
      (node (ref "D13") (pin "C") (pinfunction "C_C") (pintype "passive"))
      (node (ref "FTDI") (pin "4") (pinfunction "4_4") (pintype "passive"))
      (node (ref "J4") (pin "1") (pinfunction "1_1") (pintype "passive"))
    )
    (net (code "42") (name "/UGND") (class "Default")
      (node (ref "C12") (pin "2") (pinfunction "2_2") (pintype "passive"))
      (node (ref "C17") (pin "-") (pinfunction "-_-") (pintype "passive"))
      (node (ref "C18") (pin "1") (pinfunction "1_1") (pintype "passive"))
      (node (ref "C19") (pin "1") (pinfunction "1_1") (pintype "passive"))
      (node (ref "C20") (pin "2") (pinfunction "2_2") (pintype "passive"))
      (node (ref "C21") (pin "2") (pinfunction "2_2") (pintype "passive"))
      (node (ref "IC2") (pin "21") (pinfunction "GND_21") (pintype "power_in"))
      (node (ref "IC2") (pin "3") (pinfunction "GND_3") (pintype "power_in"))
      (node (ref "IC2") (pin "5") (pinfunction "GND_5") (pintype "power_in"))
      (node (ref "SH1") (pin "1") (pinfunction "P$1_1") (pintype "bidirectional"))
      (node (ref "SH2") (pin "2") (pinfunction "P$2_2") (pintype "bidirectional"))
    )
    (net (code "43") (name "/VCC") (class "Default")
      (node (ref "C17") (pin "+") (pinfunction "+_+") (pintype "passive"))
      (node (ref "C18") (pin "2") (pinfunction "2_2") (pintype "passive"))
      (node (ref "C19") (pin "2") (pinfunction "2_2") (pintype "passive"))
      (node (ref "IC2") (pin "4") (pinfunction "VCC_4") (pintype "power_in"))
      (node (ref "IC2") (pin "6") (pinfunction "VCC_6") (pintype "power_in"))
      (node (ref "R27") (pin "1") (pinfunction "1_1") (pintype "passive"))
    )
    (net (code "44") (name "/WELD_DETECT") (class "Default")
      (node (ref "IC2") (pin "1") (pinfunction "PD3(INT1)_1") (pintype "bidirectional"))
      (node (ref "IC8") (pin "P$6") (pinfunction "O2_P$6") (pintype "bidirectional"))
    )
    (net (code "45") (name "3.3V") (class "Default")
      (node (ref "C22") (pin "1") (pinfunction "1_1") (pintype "passive"))
      (node (ref "C23") (pin "1") (pinfunction "1_1") (pintype "passive"))
      (node (ref "C25") (pin "1") (pinfunction "1_1") (pintype "passive"))
      (node (ref "C31") (pin "1") (pinfunction "1_1") (pintype "passive"))
      (node (ref "C34") (pin "1") (pinfunction "1_1") (pintype "passive"))
      (node (ref "L1") (pin "P$2") (pinfunction "2_P$2") (pintype "passive"))
      (node (ref "LED") (pin "1") (pinfunction "1_1") (pintype "passive"))
      (node (ref "LED1") (pin "2") (pinfunction "VDD_2") (pintype "power_in"))
      (node (ref "LED2") (pin "2") (pinfunction "VDD_2") (pintype "power_in"))
      (node (ref "R13") (pin "1") (pinfunction "1_1") (pintype "passive"))
      (node (ref "SFQ") (pin "2") (pinfunction "2_2") (pintype "power_in"))
      (node (ref "U2") (pin "1") (pinfunction "FB_1") (pintype "bidirectional"))
      (node (ref "X2") (pin "2") (pinfunction "3.3V_2") (pintype "passive"))
    )
    (net (code "46") (name "ESPSCL") (class "Default")
      (node (ref "SFQ") (pin "4") (pinfunction "4_4") (pintype "passive"))
      (node (ref "X2") (pin "36") (pinfunction "IO22_36") (pintype "bidirectional"))
    )
    (net (code "47") (name "ESPSDA") (class "Default")
      (node (ref "SFQ") (pin "3") (pinfunction "3_3") (pintype "passive"))
      (node (ref "X2") (pin "33") (pinfunction "IO21_33") (pintype "bidirectional"))
    )
    (net (code "48") (name "GND") (class "Default")
      (node (ref "BOOT0") (pin "A") (pinfunction "P_A") (pintype "passive"))
      (node (ref "BOOT0") (pin "A'") (pinfunction "P1_A'") (pintype "passive"))
      (node (ref "C10") (pin "2") (pinfunction "2_2") (pintype "passive"))
      (node (ref "C11") (pin "2") (pinfunction "2_2") (pintype "passive"))
      (node (ref "C14") (pin "C") (pinfunction "-_C") (pintype "passive"))
      (node (ref "C15") (pin "1") (pinfunction "1_1") (pintype "passive"))
      (node (ref "C16") (pin "1") (pinfunction "1_1") (pintype "passive"))
      (node (ref "C22") (pin "2") (pinfunction "2_2") (pintype "passive"))
      (node (ref "C23") (pin "2") (pinfunction "2_2") (pintype "passive"))
      (node (ref "C24") (pin "2") (pinfunction "2_2") (pintype "passive"))
      (node (ref "C25") (pin "2") (pinfunction "2_2") (pintype "passive"))
      (node (ref "C26") (pin "1") (pinfunction "1_1") (pintype "passive"))
      (node (ref "C27") (pin "1") (pinfunction "1_1") (pintype "passive"))
      (node (ref "C28") (pin "2") (pinfunction "2_2") (pintype "passive"))
      (node (ref "C29") (pin "2") (pinfunction "2_2") (pintype "passive"))
      (node (ref "C3") (pin "2") (pinfunction "2_2") (pintype "passive"))
      (node (ref "C31") (pin "2") (pinfunction "2_2") (pintype "passive"))
      (node (ref "C33") (pin "2") (pinfunction "2_2") (pintype "passive"))
      (node (ref "C34") (pin "2") (pinfunction "2_2") (pintype "passive"))
      (node (ref "C35") (pin "2") (pinfunction "2_2") (pintype "passive"))
      (node (ref "C36") (pin "2") (pinfunction "2_2") (pintype "passive"))
      (node (ref "C4") (pin "2") (pinfunction "2_2") (pintype "passive"))
      (node (ref "C41") (pin "C") (pinfunction "-_C") (pintype "passive"))
      (node (ref "C42") (pin "2") (pinfunction "2_2") (pintype "passive"))
      (node (ref "C43") (pin "1") (pinfunction "1_1") (pintype "passive"))
      (node (ref "C5") (pin "2") (pinfunction "2_2") (pintype "passive"))
      (node (ref "C6") (pin "1") (pinfunction "1_1") (pintype "passive"))
      (node (ref "C8") (pin "2") (pinfunction "2_2") (pintype "passive"))
      (node (ref "C9") (pin "2") (pinfunction "2_2") (pintype "passive"))
      (node (ref "D1") (pin "1") (pinfunction "K1_1") (pintype "passive"))
      (node (ref "FTDI") (pin "1") (pinfunction "1_1") (pintype "passive"))
      (node (ref "GFCI") (pin "1") (pinfunction "1_1") (pintype "passive"))
      (node (ref "I2C") (pin "1") (pinfunction "1_1") (pintype "passive"))
      (node (ref "IC1") (pin "5") (pinfunction "+IN_5") (pintype "input"))
      (node (ref "IC3") (pin "3") (pinfunction "+IN1_3") (pintype "input"))
      (node (ref "IC3") (pin "4") (pinfunction "GND_4") (pintype "power_in"))
      (node (ref "IC4") (pin "3") (pinfunction "GND_3") (pintype "bidirectional"))
      (node (ref "IC5") (pin "10") (pinfunction "VSS_10") (pintype "power_in"))
      (node (ref "IC5") (pin "15") (pinfunction "A0_15") (pintype "input"))
      (node (ref "IC5") (pin "16") (pinfunction "A1_16") (pintype "input"))
      (node (ref "IC5") (pin "17") (pinfunction "A2_17") (pintype "input"))
      (node (ref "IC7") (pin "P$1") (pinfunction "1_P$1") (pintype "bidirectional"))
      (node (ref "IC7") (pin "P$3") (pinfunction "3_P$3") (pintype "bidirectional"))
      (node (ref "IC7") (pin "P$4") (pinfunction "4_P$4") (pintype "bidirectional"))
      (node (ref "IC8") (pin "P$5") (pinfunction "GND_P$5") (pintype "bidirectional"))
      (node (ref "ISP1") (pin "6") (pinfunction "GND_6") (pintype "power_in"))
      (node (ref "J1") (pin "1") (pinfunction "1_1") (pintype "passive"))
      (node (ref "J2") (pin "2") (pinfunction "2_2") (pintype "passive"))
      (node (ref "JP6") (pin "2") (pinfunction "2_2") (pintype "passive"))
      (node (ref "LED") (pin "2") (pinfunction "2_2") (pintype "passive"))
      (node (ref "LED1") (pin "4") (pinfunction "GND_4") (pintype "power_in"))
      (node (ref "LED2") (pin "4") (pinfunction "GND_4") (pintype "power_in"))
      (node (ref "PS1") (pin "V-") (pinfunction "V-_V-") (pintype "bidirectional"))
      (node (ref "Q2") (pin "2") (pinfunction "E_2") (pintype "passive"))
      (node (ref "R15") (pin "2") (pinfunction "2_2") (pintype "passive"))
      (node (ref "R17") (pin "1") (pinfunction "1_1") (pintype "passive"))
      (node (ref "R19") (pin "2") (pinfunction "2_2") (pintype "passive"))
      (node (ref "R21") (pin "2") (pinfunction "2_2") (pintype "passive"))
      (node (ref "R4") (pin "2") (pinfunction "2_2") (pintype "passive"))
      (node (ref "R6") (pin "2") (pinfunction "2_2") (pintype "passive"))
      (node (ref "R8") (pin "1") (pinfunction "1_1") (pintype "passive"))
      (node (ref "RESET") (pin "A") (pinfunction "P_A") (pintype "passive"))
      (node (ref "RESET") (pin "A'") (pinfunction "P1_A'") (pintype "passive"))
      (node (ref "SFQ") (pin "1") (pinfunction "1_1") (pintype "power_in"))
      (node (ref "SH1") (pin "2") (pinfunction "P$2_2") (pintype "bidirectional"))
      (node (ref "TEST_COIL") (pin "P$2") (pinfunction "P$2_P$2") (pintype "bidirectional"))
      (node (ref "TVS") (pin "A") (pinfunction "A_A") (pintype "passive"))
      (node (ref "U$9") (pin "P$1") (pinfunction "GND_P$1") (pintype "bidirectional"))
      (node (ref "U1") (pin "4") (pinfunction "GND_4") (pintype "bidirectional"))
      (node (ref "U2") (pin "4") (pinfunction "GND_4") (pintype "bidirectional"))
      (node (ref "X2") (pin "1") (pinfunction "GND_1") (pintype "passive"))
      (node (ref "X2") (pin "15") (pinfunction "GND_15") (pintype "passive"))
      (node (ref "X2") (pin "38") (pinfunction "GND_38") (pintype "passive"))
      (node (ref "X2") (pin "P$1") (pinfunction "GND_P$1") (pintype "passive"))
    )
    (net (code "49") (name "Net-(C14-+)") (class "Default")
      (node (ref "C14") (pin "A") (pinfunction "+_A") (pintype "passive"))
      (node (ref "C7") (pin "2") (pinfunction "2_2") (pintype "passive"))
      (node (ref "D3") (pin "C") (pinfunction "C_C") (pintype "passive"))
      (node (ref "R16") (pin "1") (pinfunction "1_1") (pintype "passive"))
      (node (ref "R18") (pin "2") (pinfunction "2_2") (pintype "passive"))
    )
    (net (code "50") (name "Net-(D1-K2)") (class "Default")
      (node (ref "D1") (pin "2") (pinfunction "K2_2") (pintype "passive"))
      (node (ref "GFCI") (pin "2") (pinfunction "2_2") (pintype "passive"))
      (node (ref "J1") (pin "2") (pinfunction "2_2") (pintype "passive"))
      (node (ref "R17") (pin "2") (pinfunction "2_2") (pintype "passive"))
      (node (ref "R20") (pin "2") (pinfunction "2_2") (pintype "passive"))
    )
    (net (code "51") (name "Net-(D7-PadA)") (class "Default")
      (node (ref "D7") (pin "A") (pinfunction "A_A") (pintype "passive"))
      (node (ref "R32") (pin "1") (pinfunction "1_1") (pintype "passive"))
    )
    (net (code "52") (name "Net-(D8-PadA)") (class "Default")
      (node (ref "D8") (pin "A") (pinfunction "A_A") (pintype "passive"))
      (node (ref "R34") (pin "1") (pinfunction "1_1") (pintype "passive"))
    )
    (net (code "53") (name "Net-(D9-PadA)") (class "Default")
      (node (ref "D9") (pin "A") (pinfunction "A_A") (pintype "passive"))
      (node (ref "R36") (pin "1") (pinfunction "1_1") (pintype "passive"))
    )
    (net (code "54") (name "Net-(D10-PadA)") (class "Default")
      (node (ref "D10") (pin "A") (pinfunction "A_A") (pintype "passive"))
      (node (ref "R38") (pin "1") (pinfunction "1_1") (pintype "passive"))
    )
    (net (code "55") (name "Net-(D11-K1)") (class "Default")
      (node (ref "AMP") (pin "1") (pinfunction "1_1") (pintype "passive"))
      (node (ref "C11") (pin "1") (pinfunction "1_1") (pintype "passive"))
      (node (ref "D11") (pin "1") (pinfunction "K1_1") (pintype "passive"))
      (node (ref "J3") (pin "1") (pinfunction "1_1") (pintype "passive"))
      (node (ref "R21") (pin "1") (pinfunction "1_1") (pintype "passive"))
      (node (ref "R25") (pin "2") (pinfunction "2_2") (pintype "passive"))
      (node (ref "R26") (pin "1") (pinfunction "1_1") (pintype "passive"))
    )
    (net (code "56") (name "Net-(IC1A--IN)") (class "Default")
      (node (ref "C15") (pin "2") (pinfunction "2_2") (pintype "passive"))
      (node (ref "IC1") (pin "2") (pinfunction "-IN_2") (pintype "input"))
      (node (ref "R8") (pin "2") (pinfunction "2_2") (pintype "passive"))
      (node (ref "R9") (pin "2") (pinfunction "2_2") (pintype "passive"))
    )
    (net (code "57") (name "Net-(IC1A-OUT)") (class "Default")
      (node (ref "IC1") (pin "1") (pinfunction "OUT_1") (pintype "output"))
      (node (ref "R1") (pin "2") (pinfunction "2_2") (pintype "passive"))
    )
    (net (code "58") (name "Net-(IC1B--IN)") (class "Default")
      (node (ref "IC1") (pin "6") (pinfunction "-IN_6") (pintype "input"))
      (node (ref "IC1") (pin "7") (pinfunction "OUT_7") (pintype "output"))
    )
    (net (code "59") (name "Net-(IC1C-P$V-)") (class "Default")
      (node (ref "C26") (pin "2") (pinfunction "2_2") (pintype "passive"))
      (node (ref "C5") (pin "1") (pinfunction "1_1") (pintype "passive"))
      (node (ref "IC1") (pin "4") (pinfunction "P$V-_4") (pintype "bidirectional"))
      (node (ref "IC4") (pin "5") (pinfunction "VOUT_5") (pintype "bidirectional"))
    )
    (net (code "60") (name "Net-(IC2-PB6(XTAL1{slash}TOSC1))") (class "Default")
      (node (ref "C1") (pin "2") (pinfunction "2_2") (pintype "passive"))
      (node (ref "IC2") (pin "7") (pinfunction "PB6(XTAL1/TOSC1)_7") (pintype "bidirectional"))
      (node (ref "Q1") (pin "2") (pinfunction "X1_2") (pintype "bidirectional"))
    )
    (net (code "61") (name "Net-(IC2-PB7(XTAL2{slash}TOSC2))") (class "Default")
      (node (ref "C2") (pin "1") (pinfunction "1_1") (pintype "passive"))
      (node (ref "IC2") (pin "8") (pinfunction "PB7(XTAL2/TOSC2)_8") (pintype "bidirectional"))
      (node (ref "Q1") (pin "4") (pinfunction "X2_4") (pintype "bidirectional"))
    )
    (net (code "62") (name "Net-(IC2-PD1(TXD))") (class "Default")
      (node (ref "IC2") (pin "31") (pinfunction "PD1(TXD)_31") (pintype "bidirectional"))
      (node (ref "J4") (pin "2") (pinfunction "2_2") (pintype "passive"))
    )
    (net (code "63") (name "Net-(IC2-PD7(AIN1))") (class "Default")
      (node (ref "IC2") (pin "11") (pinfunction "PD7(AIN1)_11") (pintype "bidirectional"))
      (node (ref "R31") (pin "1") (pinfunction "1_1") (pintype "passive"))
    )
    (net (code "64") (name "Net-(IC3A--IN1)") (class "Default")
      (node (ref "C7") (pin "1") (pinfunction "1_1") (pintype "passive"))
      (node (ref "IC3") (pin "2") (pinfunction "-IN1_2") (pintype "input"))
      (node (ref "R16") (pin "2") (pinfunction "2_2") (pintype "passive"))
      (node (ref "R20") (pin "1") (pinfunction "1_1") (pintype "passive"))
    )
    (net (code "65") (name "Net-(IC3A-OUT1)") (class "Default")
      (node (ref "D3") (pin "A") (pinfunction "A_A") (pintype "passive"))
      (node (ref "IC3") (pin "1") (pinfunction "OUT1_1") (pintype "output"))
    )
    (net (code "66") (name "Net-(IC3B-+IN2)") (class "Default")
      (node (ref "IC3") (pin "5") (pinfunction "+IN2_5") (pintype "input"))
      (node (ref "R18") (pin "1") (pinfunction "1_1") (pintype "passive"))
    )
    (net (code "67") (name "Net-(IC3B--IN2)") (class "Default")
      (node (ref "C16") (pin "2") (pinfunction "2_2") (pintype "passive"))
      (node (ref "IC3") (pin "6") (pinfunction "-IN2_6") (pintype "input"))
      (node (ref "R14") (pin "2") (pinfunction "2_2") (pintype "passive"))
      (node (ref "R15") (pin "1") (pinfunction "1_1") (pintype "passive"))
    )
    (net (code "68") (name "Net-(IC3B-OUT2)") (class "Default")
      (node (ref "D4") (pin "A") (pinfunction "A_A") (pintype "passive"))
      (node (ref "IC3") (pin "7") (pinfunction "OUT2_7") (pintype "output"))
    )
    (net (code "69") (name "Net-(IC4-CAP+)") (class "Default")
      (node (ref "C13") (pin "2") (pinfunction "2_2") (pintype "passive"))
      (node (ref "IC4") (pin "2") (pinfunction "CAP+_2") (pintype "bidirectional"))
    )
    (net (code "70") (name "Net-(IC4-CAP-)") (class "Default")
      (node (ref "C13") (pin "1") (pinfunction "1_1") (pintype "passive"))
      (node (ref "IC4") (pin "4") (pinfunction "CAP-_4") (pintype "bidirectional"))
    )
    (net (code "71") (name "Net-(IC7-2)") (class "Default")
      (node (ref "IC7") (pin "P$2") (pinfunction "2_P$2") (pintype "bidirectional"))
      (node (ref "R29") (pin "1") (pinfunction "1_1") (pintype "passive"))
    )
    (net (code "72") (name "Net-(IC8-I1+)") (class "Default")
      (node (ref "D7") (pin "C") (pinfunction "C_C") (pintype "passive"))
      (node (ref "D8") (pin "C") (pinfunction "C_C") (pintype "passive"))
      (node (ref "IC8") (pin "P$1") (pinfunction "I1+_P$1") (pintype "bidirectional"))
    )
    (net (code "73") (name "Net-(IC8-I2+)") (class "Default")
      (node (ref "D10") (pin "C") (pinfunction "C_C") (pintype "passive"))
      (node (ref "D9") (pin "C") (pinfunction "C_C") (pintype "passive"))
      (node (ref "IC8") (pin "P$4") (pinfunction "I2+_P$4") (pintype "bidirectional"))
    )
    (net (code "74") (name "Net-(J2-Pad1)") (class "Default")
      (node (ref "J2") (pin "1") (pinfunction "1_1") (pintype "passive"))
      (node (ref "R23") (pin "2") (pinfunction "2_2") (pintype "passive"))
      (node (ref "TEST_COIL") (pin "P$1") (pinfunction "P$1_P$1") (pintype "bidirectional"))
    )
    (net (code "75") (name "Net-(L1-1)") (class "Default")
      (node (ref "C30") (pin "2") (pinfunction "2_2") (pintype "passive"))
      (node (ref "L1") (pin "P$1") (pinfunction "1_P$1") (pintype "passive"))
      (node (ref "U2") (pin "5") (pinfunction "SW_5") (pintype "bidirectional"))
    )
    (net (code "76") (name "Net-(L2-1)") (class "Default")
      (node (ref "C32") (pin "2") (pinfunction "2_2") (pintype "passive"))
      (node (ref "L2") (pin "P$1") (pinfunction "1_P$1") (pintype "passive"))
      (node (ref "U1") (pin "5") (pinfunction "SW_5") (pintype "bidirectional"))
    )
    (net (code "77") (name "Net-(L3-Pad2)") (class "Default")
      (node (ref "L3") (pin "2") (pinfunction "2_2") (pintype "passive"))
      (node (ref "R27") (pin "2") (pinfunction "2_2") (pintype "passive"))
    )
    (net (code "78") (name "Net-(LED1-DO)") (class "Default")
      (node (ref "LED1") (pin "3") (pinfunction "DO_3") (pintype "output"))
      (node (ref "LED2") (pin "1") (pinfunction "DI_1") (pintype "input"))
    )
    (net (code "79") (name "Net-(Q1-G1)") (class "Default")
      (node (ref "C1") (pin "1") (pinfunction "1_1") (pintype "passive"))
      (node (ref "C2") (pin "2") (pinfunction "2_2") (pintype "passive"))
      (node (ref "Q1") (pin "1") (pinfunction "G1_1") (pintype "power_in"))
      (node (ref "Q1") (pin "3") (pinfunction "G2_3") (pintype "power_in"))
      (node (ref "SH2") (pin "1") (pinfunction "P$1_1") (pintype "bidirectional"))
    )
    (net (code "80") (name "Net-(Q2-B)") (class "Default")
      (node (ref "Q2") (pin "1") (pinfunction "B_1") (pintype "passive"))
      (node (ref "R24") (pin "1") (pinfunction "1_1") (pintype "passive"))
    )
    (net (code "81") (name "Net-(Q2-C)") (class "Default")
      (node (ref "D5") (pin "A") (pinfunction "A_A") (pintype "passive"))
      (node (ref "JP7") (pin "1") (pinfunction "1_1") (pintype "passive"))
      (node (ref "PILOT") (pin "P$2") (pinfunction "P$2_P$2") (pintype "bidirectional"))
      (node (ref "Q2") (pin "3") (pinfunction "C_3") (pintype "passive"))
    )
    (net (code "82") (name "Net-(R32-Pad2)") (class "Default")
      (node (ref "R32") (pin "2") (pinfunction "2_2") (pintype "passive"))
      (node (ref "R33") (pin "1") (pinfunction "1_1") (pintype "passive"))
    )
    (net (code "83") (name "Net-(R34-Pad2)") (class "Default")
      (node (ref "R34") (pin "2") (pinfunction "2_2") (pintype "passive"))
      (node (ref "R35") (pin "1") (pinfunction "1_1") (pintype "passive"))
    )
    (net (code "84") (name "Net-(R36-Pad2)") (class "Default")
      (node (ref "R36") (pin "2") (pinfunction "2_2") (pintype "passive"))
      (node (ref "R37") (pin "1") (pinfunction "1_1") (pintype "passive"))
    )
    (net (code "85") (name "Net-(R38-Pad2)") (class "Default")
      (node (ref "R38") (pin "2") (pinfunction "2_2") (pintype "passive"))
      (node (ref "R39") (pin "1") (pinfunction "1_1") (pintype "passive"))
    )
    (net (code "86") (name "Net-(RGB_LED-1)") (class "Default")
      (node (ref "R4") (pin "1") (pinfunction "1_1") (pintype "passive"))
      (node (ref "RGB_LED") (pin "P$1") (pinfunction "1_P$1") (pintype "bidirectional"))
    )
    (net (code "87") (name "Net-(RGB_LED-2)") (class "Default")
      (node (ref "R3") (pin "1") (pinfunction "1_1") (pintype "passive"))
      (node (ref "RGB_LED") (pin "P$2") (pinfunction "2_P$2") (pintype "bidirectional"))
    )
    (net (code "88") (name "Net-(RGB_LED-3)") (class "Default")
      (node (ref "R2") (pin "1") (pinfunction "1_1") (pintype "passive"))
      (node (ref "RGB_LED") (pin "P$3") (pinfunction "3_P$3") (pintype "bidirectional"))
    )
    (net (code "89") (name "Net-(U1-BST)") (class "Default")
      (node (ref "C32") (pin "1") (pinfunction "1_1") (pintype "passive"))
      (node (ref "U1") (pin "6") (pinfunction "BST_6") (pintype "bidirectional"))
    )
    (net (code "90") (name "Net-(U2-BST)") (class "Default")
      (node (ref "C30") (pin "1") (pinfunction "1_1") (pintype "passive"))
      (node (ref "U2") (pin "6") (pinfunction "BST_6") (pintype "bidirectional"))
    )
    (net (code "91") (name "PE") (class "Default")
      (node (ref "C37") (pin "P$1") (pinfunction "1_P$1") (pintype "passive"))
      (node (ref "C38") (pin "P$1") (pinfunction "1_P$1") (pintype "passive"))
      (node (ref "G1") (pin "1") (pinfunction "1_1") (pintype "passive"))
      (node (ref "IC8") (pin "P$2") (pinfunction "I1-_P$2") (pintype "bidirectional"))
      (node (ref "IC8") (pin "P$3") (pinfunction "I2-_P$3") (pintype "bidirectional"))
      (node (ref "M3") (pin "P$1") (pinfunction "1_P$1") (pintype "passive"))
      (node (ref "M4") (pin "P$1") (pinfunction "1_P$1") (pintype "passive"))
      (node (ref "U$3") (pin "P$1") (pinfunction "GND_P$1") (pintype "bidirectional"))
    )
    (net (code "92") (name "unconnected-(D1-AA-Pad3)") (class "Default")
      (node (ref "D1") (pin "3") (pinfunction "AA_3") (pintype "passive"))
    )
    (net (code "93") (name "unconnected-(D11-AA-Pad3)") (class "Default")
      (node (ref "D11") (pin "3") (pinfunction "AA_3") (pintype "passive"))
    )
    (net (code "94") (name "unconnected-(FTDI-Pad2)") (class "Default")
      (node (ref "FTDI") (pin "2") (pinfunction "2_2") (pintype "passive"))
    )
    (net (code "95") (name "unconnected-(IC4-LV-Pad6)") (class "Default")
      (node (ref "IC4") (pin "6") (pinfunction "LV_6") (pintype "bidirectional"))
    )
    (net (code "96") (name "unconnected-(IC4-OSC-Pad7)") (class "Default")
      (node (ref "IC4") (pin "7") (pinfunction "OSC_7") (pintype "bidirectional"))
    )
    (net (code "97") (name "unconnected-(IC5-GPA0-Pad21)") (class "Default")
      (node (ref "IC5") (pin "21") (pinfunction "GPA0_21") (pintype "bidirectional"))
    )
    (net (code "98") (name "unconnected-(IC5-GPA1-Pad22)") (class "Default")
      (node (ref "IC5") (pin "22") (pinfunction "GPA1_22") (pintype "bidirectional"))
    )
    (net (code "99") (name "unconnected-(IC5-GPA2-Pad23)") (class "Default")
      (node (ref "IC5") (pin "23") (pinfunction "GPA2_23") (pintype "bidirectional"))
    )
    (net (code "100") (name "unconnected-(IC5-GPA3-Pad24)") (class "Default")
      (node (ref "IC5") (pin "24") (pinfunction "GPA3_24") (pintype "bidirectional"))
    )
    (net (code "101") (name "unconnected-(IC5-GPA4-Pad25)") (class "Default")
      (node (ref "IC5") (pin "25") (pinfunction "GPA4_25") (pintype "bidirectional"))
    )
    (net (code "102") (name "unconnected-(IC5-GPA5-Pad26)") (class "Default")
      (node (ref "IC5") (pin "26") (pinfunction "GPA5_26") (pintype "bidirectional"))
    )
    (net (code "103") (name "unconnected-(IC5-GPB1-Pad2)") (class "Default")
      (node (ref "IC5") (pin "2") (pinfunction "GPB1_2") (pintype "bidirectional"))
    )
    (net (code "104") (name "unconnected-(IC5-GPB2-Pad3)") (class "Default")
      (node (ref "IC5") (pin "3") (pinfunction "GPB2_3") (pintype "bidirectional"))
    )
    (net (code "105") (name "unconnected-(IC5-GPB3-Pad4)") (class "Default")
      (node (ref "IC5") (pin "4") (pinfunction "GPB3_4") (pintype "bidirectional"))
    )
    (net (code "106") (name "unconnected-(IC5-GPB4-Pad5)") (class "Default")
      (node (ref "IC5") (pin "5") (pinfunction "GPB4_5") (pintype "bidirectional"))
    )
    (net (code "107") (name "unconnected-(IC5-GPB5-Pad6)") (class "Default")
      (node (ref "IC5") (pin "6") (pinfunction "GPB5_6") (pintype "bidirectional"))
    )
    (net (code "108") (name "unconnected-(IC5-GPB6-Pad7)") (class "Default")
      (node (ref "IC5") (pin "7") (pinfunction "GPB6_7") (pintype "bidirectional"))
    )
    (net (code "109") (name "unconnected-(IC5-GPB7-Pad8)") (class "Default")
      (node (ref "IC5") (pin "8") (pinfunction "GPB7_8") (pintype "bidirectional"))
    )
    (net (code "110") (name "unconnected-(IC5-INTA-Pad20)") (class "Default")
      (node (ref "IC5") (pin "20") (pinfunction "INTA_20") (pintype "output"))
    )
    (net (code "111") (name "unconnected-(IC5-INTB-Pad19)") (class "Default")
      (node (ref "IC5") (pin "19") (pinfunction "INTB_19") (pintype "output"))
    )
    (net (code "112") (name "unconnected-(IC7-5-PadP$5)") (class "Default")
      (node (ref "IC7") (pin "P$5") (pinfunction "5_P$5") (pintype "bidirectional"))
    )
    (net (code "113") (name "unconnected-(X2-CLK-Pad20)") (class "Default")
      (node (ref "X2") (pin "20") (pinfunction "CLK_20") (pintype "bidirectional"))
    )
    (net (code "114") (name "unconnected-(X2-CMD-Pad19)") (class "Default")
      (node (ref "X2") (pin "19") (pinfunction "CMD_19") (pintype "bidirectional"))
    )
    (net (code "115") (name "unconnected-(X2-I34{slash}A1_6-Pad6)") (class "Default")
      (node (ref "X2") (pin "6") (pinfunction "I34/A1_6_6") (pintype "bidirectional"))
    )
    (net (code "116") (name "unconnected-(X2-I35{slash}A1_7-Pad7)") (class "Default")
      (node (ref "X2") (pin "7") (pinfunction "I35/A1_7_7") (pintype "bidirectional"))
    )
    (net (code "117") (name "unconnected-(X2-IO2{slash}A2_2-Pad24)") (class "Default")
      (node (ref "X2") (pin "24") (pinfunction "IO2/A2_2_24") (pintype "bidirectional"))
    )
    (net (code "118") (name "unconnected-(X2-IO4{slash}A2_0-Pad26)") (class "Default")
      (node (ref "X2") (pin "26") (pinfunction "IO4/A2_0_26") (pintype "bidirectional"))
    )
    (net (code "119") (name "unconnected-(X2-IO5-Pad29)") (class "Default")
      (node (ref "X2") (pin "29") (pinfunction "IO5_29") (pintype "bidirectional"))
    )
    (net (code "120") (name "unconnected-(X2-IO12{slash}A2_5-Pad14)") (class "Default")
      (node (ref "X2") (pin "14") (pinfunction "IO12/A2_5_14") (pintype "bidirectional"))
    )
    (net (code "121") (name "unconnected-(X2-IO13{slash}A2_4-Pad16)") (class "Default")
      (node (ref "X2") (pin "16") (pinfunction "IO13/A2_4_16") (pintype "bidirectional"))
    )
    (net (code "122") (name "unconnected-(X2-IO14{slash}A2_6-Pad13)") (class "Default")
      (node (ref "X2") (pin "13") (pinfunction "IO14/A2_6_13") (pintype "bidirectional"))
    )
    (net (code "123") (name "unconnected-(X2-IO15{slash}A2_3-Pad23)") (class "Default")
      (node (ref "X2") (pin "23") (pinfunction "IO15/A2_3_23") (pintype "bidirectional"))
    )
    (net (code "124") (name "unconnected-(X2-IO16-Pad27)") (class "Default")
      (node (ref "X2") (pin "27") (pinfunction "IO16_27") (pintype "bidirectional"))
    )
    (net (code "125") (name "unconnected-(X2-IO18-Pad30)") (class "Default")
      (node (ref "X2") (pin "30") (pinfunction "IO18_30") (pintype "bidirectional"))
    )
    (net (code "126") (name "unconnected-(X2-IO19-Pad31)") (class "Default")
      (node (ref "X2") (pin "31") (pinfunction "IO19_31") (pintype "bidirectional"))
    )
    (net (code "127") (name "unconnected-(X2-IO23-Pad37)") (class "Default")
      (node (ref "X2") (pin "37") (pinfunction "IO23_37") (pintype "bidirectional"))
    )
    (net (code "128") (name "unconnected-(X2-IO25{slash}DAC1{slash}A2_8-Pad10)") (class "Default")
      (node (ref "X2") (pin "10") (pinfunction "IO25/DAC1/A2_8_10") (pintype "bidirectional"))
    )
    (net (code "129") (name "unconnected-(X2-IO26{slash}DAC2{slash}A2_9-Pad11)") (class "Default")
      (node (ref "X2") (pin "11") (pinfunction "IO26/DAC2/A2_9_11") (pintype "bidirectional"))
    )
    (net (code "130") (name "unconnected-(X2-IO27{slash}A2_7-Pad12)") (class "Default")
      (node (ref "X2") (pin "12") (pinfunction "IO27/A2_7_12") (pintype "bidirectional"))
    )
    (net (code "131") (name "unconnected-(X2-IO32{slash}A1_4{slash}X32P-Pad8)") (class "Default")
      (node (ref "X2") (pin "8") (pinfunction "IO32/A1_4/X32P_8") (pintype "bidirectional"))
    )
    (net (code "132") (name "unconnected-(X2-IO33{slash}A1_5{slash}X32N-Pad9)") (class "Default")
      (node (ref "X2") (pin "9") (pinfunction "IO33/A1_5/X32N_9") (pintype "bidirectional"))
    )
    (net (code "133") (name "unconnected-(X2-IO36{slash}SEN_VP{slash}A1_0-Pad4)") (class "Default")
      (node (ref "X2") (pin "4") (pinfunction "IO36/SEN_VP/A1_0_4") (pintype "passive"))
    )
    (net (code "134") (name "unconnected-(X2-IO39{slash}SEN_VN{slash}A1_3-Pad5)") (class "Default")
      (node (ref "X2") (pin "5") (pinfunction "IO39/SEN_VN/A1_3_5") (pintype "passive"))
    )
    (net (code "135") (name "unconnected-(X2-SD0-Pad21)") (class "Default")
      (node (ref "X2") (pin "21") (pinfunction "SD0_21") (pintype "bidirectional"))
    )
    (net (code "136") (name "unconnected-(X2-SD1-Pad22)") (class "Default")
      (node (ref "X2") (pin "22") (pinfunction "SD1_22") (pintype "bidirectional"))
    )
    (net (code "137") (name "unconnected-(X2-SD2-Pad17)") (class "Default")
      (node (ref "X2") (pin "17") (pinfunction "SD2_17") (pintype "bidirectional"))
    )
    (net (code "138") (name "unconnected-(X2-SD3-Pad18)") (class "Default")
      (node (ref "X2") (pin "18") (pinfunction "SD3_18") (pintype "bidirectional"))
    )
  )
)
